# Mcu.net
KiCad netlist of a schematic drawn in Altium Designer
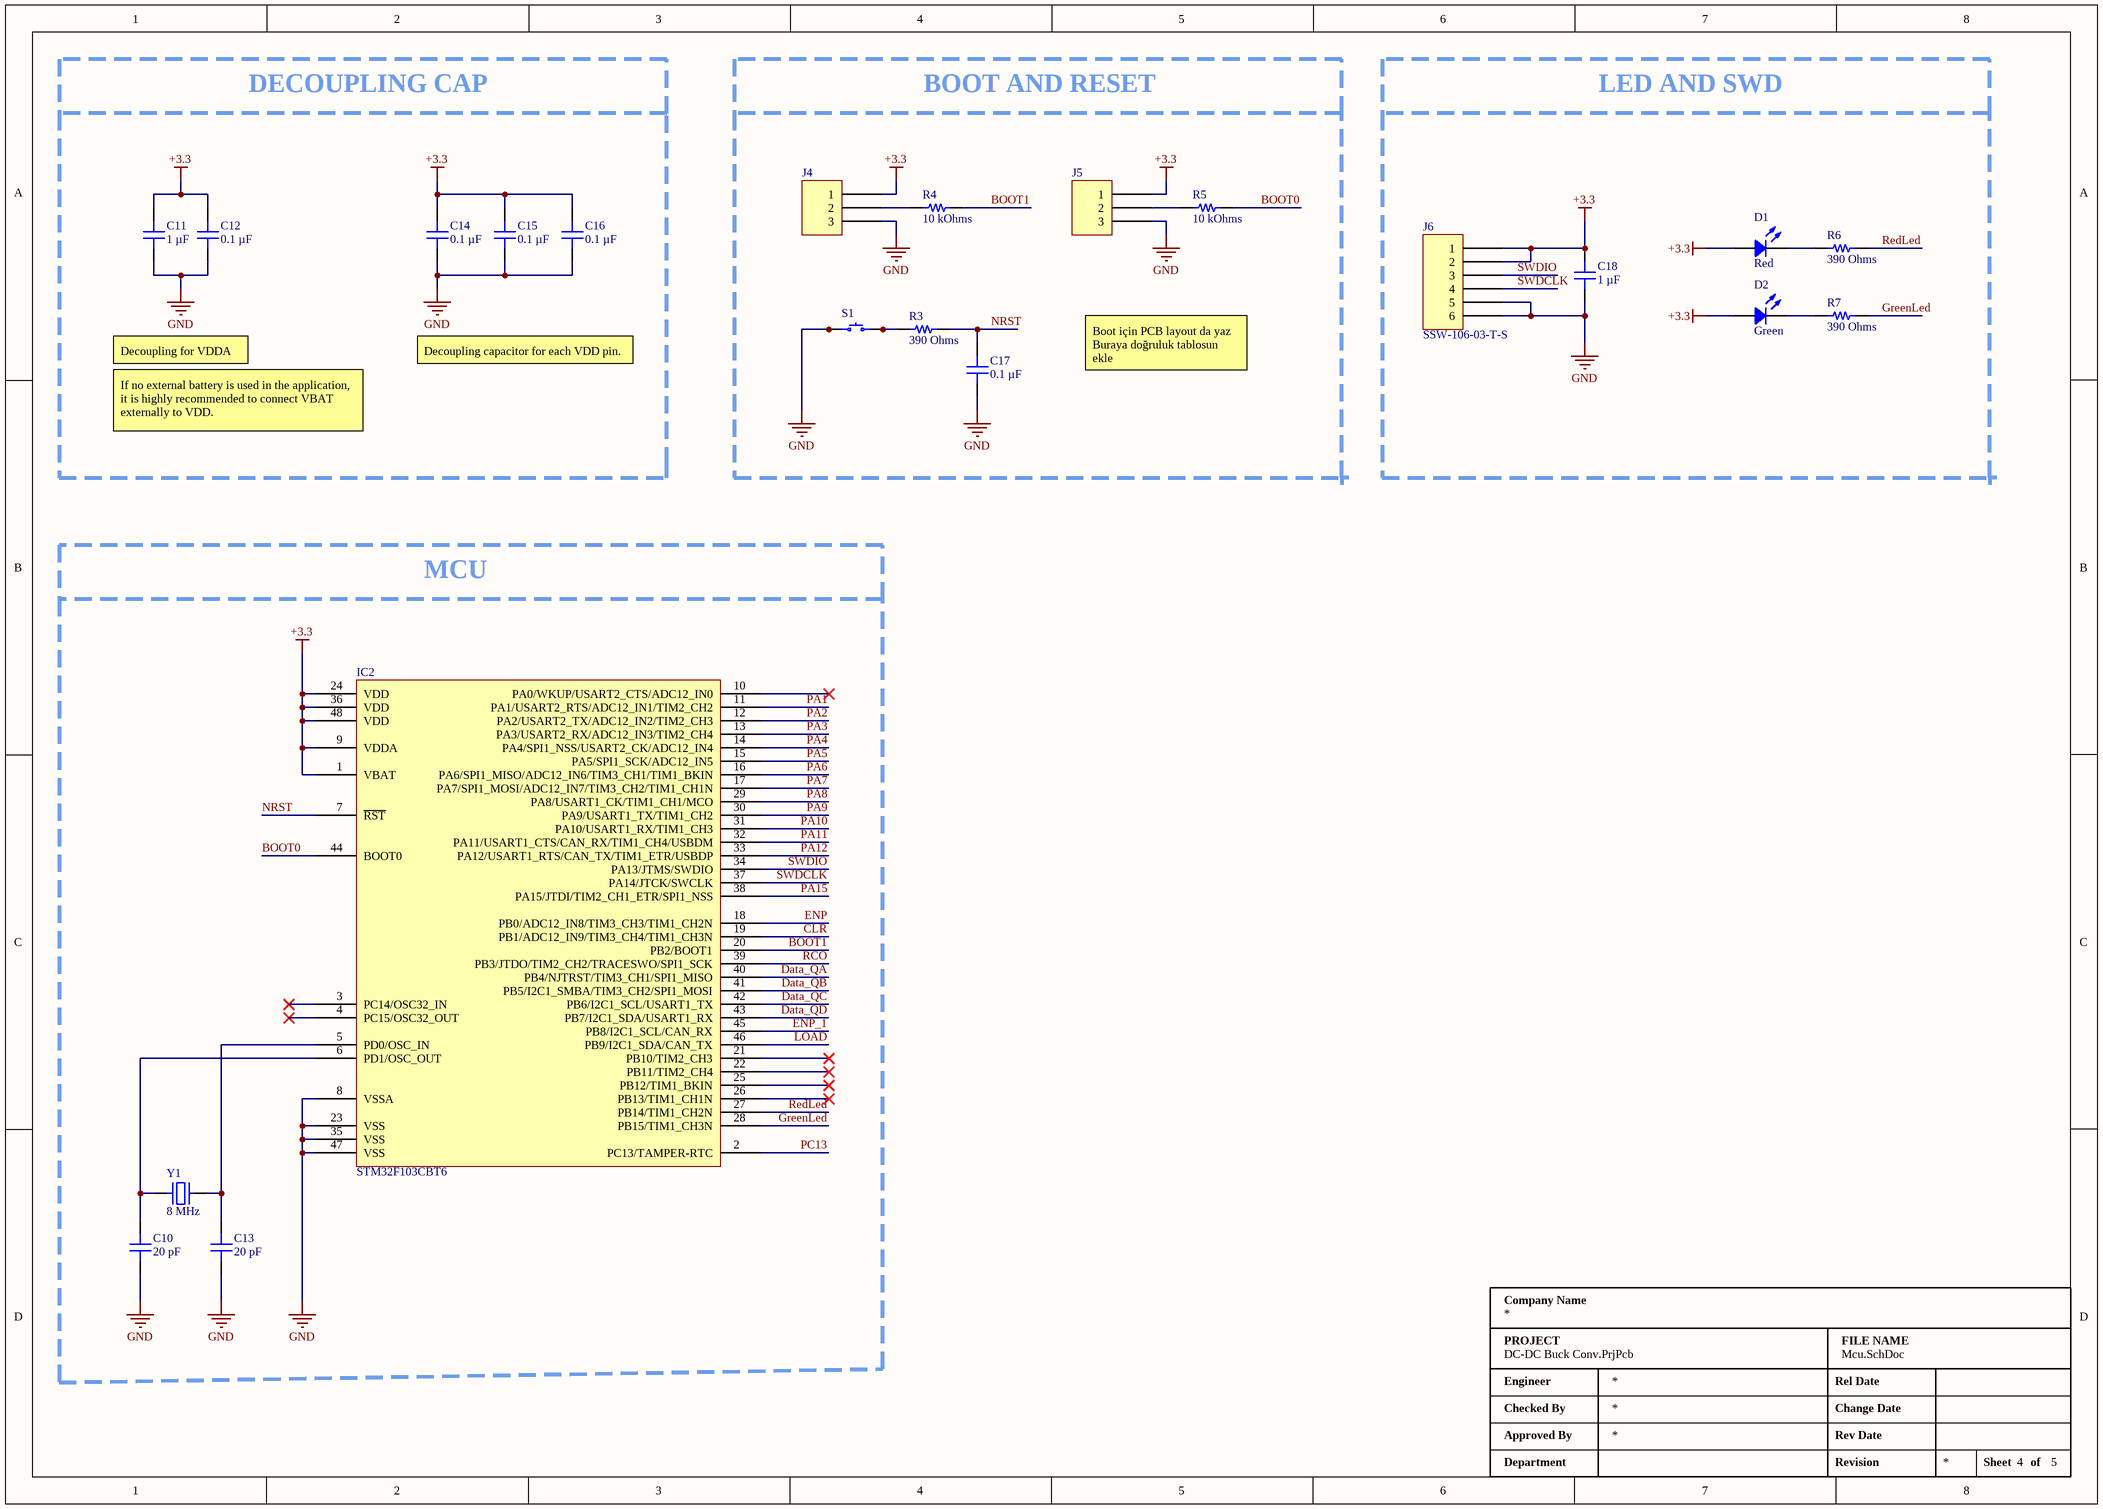
[diagram p0: Mcu.SchDoc]

(export (version "E")
  (design (tool "Eeschema 10.0.6"))
  (components
    (comp (ref "C10")
      (value "20 pF")
      (footprint "CAP 0805_2012")
      (description "CAP CER SMD 0805 20PF 50V 1% COG")
      (fields
        (field (name "PART NUMBER") "C0805C200F5GAC7800")
        (field (name "CAPACITANCE") "20 pF")
        (field (name "MANUFACTURER") "KEMET")
      )
      (libsource (lib "Celestial Altium Library - altium_library") (part "Capacitor"))
    )
    (comp (ref "C11")
      (value "1 µF")
      (footprint "CAP 0603_1608")
      (description "CAP CER 0603 1UF 16V X7R 20%")
      (fields
        (field (name "PART NUMBER") "C0603X105M4RAC7867")
        (field (name "CAPACITANCE") "1 µF")
        (field (name "MANUFACTURER") "KEMET")
      )
      (libsource (lib "Celestial Altium Library - altium_library") (part "Capacitor"))
    )
    (comp (ref "C12")
      (value "0.1 µF")
      (footprint "CAP 0805_2012")
      (description "CAP CER 0805 0.1UF 100V X7R 5%")
      (fields
        (field (name "PART NUMBER") "C0805C104J1RECAUTO")
        (field (name "CAPACITANCE") "0.1 µF")
        (field (name "MANUFACTURER") "KEMET")
      )
      (libsource (lib "Celestial Altium Library - altium_library") (part "Capacitor"))
    )
    (comp (ref "C13")
      (value "20 pF")
      (footprint "CAP 0805_2012")
      (description "CAP CER SMD 0805 20PF 50V 1% COG")
      (fields
        (field (name "PART NUMBER") "C0805C200F5GAC7800")
        (field (name "CAPACITANCE") "20 pF")
        (field (name "MANUFACTURER") "KEMET")
      )
      (libsource (lib "Celestial Altium Library - altium_library") (part "Capacitor"))
    )
    (comp (ref "C14")
      (value "0.1 µF")
      (footprint "CAP 0805_2012")
      (description "CAP CER 0805 0.1UF 100V X7R 5%")
      (fields
        (field (name "PART NUMBER") "C0805C104J1RECAUTO")
        (field (name "CAPACITANCE") "0.1 µF")
        (field (name "MANUFACTURER") "KEMET")
      )
      (libsource (lib "Celestial Altium Library - altium_library") (part "Capacitor"))
    )
    (comp (ref "C15")
      (value "0.1 µF")
      (footprint "CAP 0805_2012")
      (description "CAP CER 0805 0.1UF 100V X7R 5%")
      (fields
        (field (name "PART NUMBER") "C0805C104J1RECAUTO")
        (field (name "CAPACITANCE") "0.1 µF")
        (field (name "MANUFACTURER") "KEMET")
      )
      (libsource (lib "Celestial Altium Library - altium_library") (part "Capacitor"))
    )
    (comp (ref "C16")
      (value "0.1 µF")
      (footprint "CAP 0805_2012")
      (description "CAP CER 0805 0.1UF 100V X7R 5%")
      (fields
        (field (name "PART NUMBER") "C0805C104J1RECAUTO")
        (field (name "CAPACITANCE") "0.1 µF")
        (field (name "MANUFACTURER") "KEMET")
      )
      (libsource (lib "Celestial Altium Library - altium_library") (part "Capacitor"))
    )
    (comp (ref "C17")
      (value "0.1 µF")
      (footprint "CAP 0805_2012")
      (description "CAP CER 0805 0.1UF 100V X7R 5%")
      (fields
        (field (name "PART NUMBER") "C0805C104J1RECAUTO")
        (field (name "CAPACITANCE") "0.1 µF")
        (field (name "MANUFACTURER") "KEMET")
      )
      (libsource (lib "Celestial Altium Library - altium_library") (part "Capacitor"))
    )
    (comp (ref "C18")
      (value "1 µF")
      (footprint "CAP 0603_1608")
      (description "CAP CER 0603 1UF 16V X7R 20%")
      (fields
        (field (name "PART NUMBER") "C0603X105M4RAC7867")
        (field (name "CAPACITANCE") "1 µF")
        (field (name "MANUFACTURER") "KEMET")
      )
      (libsource (lib "Celestial Altium Library - altium_library") (part "Capacitor"))
    )
    (comp (ref "D1")
      (value "Red")
      (footprint "LED 0805_2012 RED")
      (description "LED RED CLEAR 0805 SMD")
      (fields
        (field (name "PART NUMBER") "CMD17-21SRC/TR8")
        (field (name "MANUFACTURER") "Visual Communications Company - VCC")
      )
      (libsource (lib "Celestial Altium Library - altium_library") (part "LED"))
    )
    (comp (ref "D2")
      (value "Green")
      (footprint "LED 0805_2012 RED")
      (description "LED RED CLEAR 0805 SMD")
      (fields
        (field (name "PART NUMBER") "CMD17-21SRC/TR8")
        (field (name "MANUFACTURER") "Visual Communications Company - VCC")
      )
      (libsource (lib "Celestial Altium Library - altium_library") (part "LED"))
    )
    (comp (ref "IC2")
      (value "STM32F103CBT6")
      (footprint "ST LQFP-48 7X7MM")
      (description "IC MCU 32BIT 128KB FLASH 48LQFP")
      (fields (field (name "MANUFACTURER") "STMicroelectronics"))
      (libsource (lib "Celestial Altium Library - altium_library") (part "ST STM32F103 48PIN"))
    )
    (comp (ref "J4")
      (value "61300311121")
      (footprint "WURTH WE-PHD 61300311121")
      (description "CONN HEADER VERT 3POS 2.54MM")
      (fields (field (name "MANUFACTURER") "Würth Elektronik"))
      (libsource (lib "Celestial Altium Library - altium_library") (part "3 Pin"))
    )
    (comp (ref "J5")
      (value "61300311121")
      (footprint "WURTH WE-PHD 61300311121")
      (description "CONN HEADER VERT 3POS 2.54MM")
      (fields (field (name "MANUFACTURER") "Würth Elektronik"))
      (libsource (lib "Celestial Altium Library - altium_library") (part "3 Pin"))
    )
    (comp (ref "J6")
      (value "SSW-106-03-T-S")
      (footprint "SAMTEC SSW-106-03-T-S")
      (description "CONN RCPT 6POS 0.1 TIN PCB")
      (fields (field (name "MANUFACTURER") "Samtec Inc."))
      (libsource (lib "Celestial Altium Library - altium_library") (part "6 Pin"))
    )
    (comp (ref "R3")
      (value "390 Ohms")
      (footprint "KOA RES RK73 RN73 0603_1608")
      (description "RESISTOR")
      (fields
        (field (name "PART NUMBER") "RK73B1JTTDD391J")
        (field (name "MANUFACTURER") "KOA Speer Electronics, Inc.")
      )
      (libsource (lib "Celestial Altium Library - altium_library") (part "Resistor"))
    )
    (comp (ref "R4")
      (value "10 kOhms")
      (footprint "YAGEO RES 0603_1608")
      (description "RES SMD 10K OHM 1% 1/10W 0603")
      (fields (field (name "PART NUMBER") "AT0603FRE0710KL") (field (name "MANUFACTURER") "Yageo"))
      (libsource (lib "Celestial Altium Library - altium_library") (part "Resistor"))
    )
    (comp (ref "R5")
      (value "10 kOhms")
      (footprint "YAGEO RES 0603_1608")
      (description "RES SMD 10K OHM 1% 1/10W 0603")
      (fields (field (name "PART NUMBER") "AT0603FRE0710KL") (field (name "MANUFACTURER") "Yageo"))
      (libsource (lib "Celestial Altium Library - altium_library") (part "Resistor"))
    )
    (comp (ref "R6")
      (value "390 Ohms")
      (footprint "KOA RES RK73 RN73 0603_1608")
      (description "RESISTOR")
      (fields
        (field (name "PART NUMBER") "RK73B1JTTDD391J")
        (field (name "MANUFACTURER") "KOA Speer Electronics, Inc.")
      )
      (libsource (lib "Celestial Altium Library - altium_library") (part "Resistor"))
    )
    (comp (ref "R7")
      (value "390 Ohms")
      (footprint "KOA RES RK73 RN73 0603_1608")
      (description "RESISTOR")
      (fields
        (field (name "PART NUMBER") "RK73B1JTTDD391J")
        (field (name "MANUFACTURER") "KOA Speer Electronics, Inc.")
      )
      (libsource (lib "Celestial Altium Library - altium_library") (part "Resistor"))
    )
    (comp (ref "S1")
      (value "PTS645SM43SMTR92 LFS")
      (footprint "C&K PTS645")
      (description "SWITCH TACTILE SPST-NO 0.05A 12V")
      (fields (field (name "MANUFACTURER") "C&K"))
      (libsource (lib "Celestial Altium Library - altium_library") (part "SPST-NO 4 PIN"))
    )
    (comp (ref "Y1")
      (value "8 MHz")
      (footprint "NDK NX5032GA")
      (description "CRYSTAL 8.0000MHZ 18PF SMD")
      (fields
        (field (name "PART NUMBER") "NX5032GA-8MHZ-EXS00A-CG07039")
        (field (name "MANUFACTURER") "NDK America, Inc.")
      )
      (libsource (lib "Celestial Altium Library - altium_library") (part "NDK Crystal NX5032GA"))
    )
  )
  (nets
    (net (code "1") (name "+3.3") (class "Default")
      (node (ref "C11") (pin "2") (pinfunction "2_2") (pintype "passive"))
      (node (ref "C12") (pin "2") (pinfunction "2_2") (pintype "passive"))
      (node (ref "C14") (pin "2") (pinfunction "2_2") (pintype "passive"))
      (node (ref "C15") (pin "2") (pinfunction "2_2") (pintype "passive"))
      (node (ref "C16") (pin "2") (pinfunction "2_2") (pintype "passive"))
      (node (ref "C18") (pin "2") (pinfunction "2_2") (pintype "passive"))
      (node (ref "D1") (pin "1") (pinfunction "1_1") (pintype "passive"))
      (node (ref "D2") (pin "1") (pinfunction "1_1") (pintype "passive"))
      (node (ref "IC2") (pin "1") (pinfunction "VBAT_1") (pintype "passive"))
      (node (ref "IC2") (pin "24") (pinfunction "VDD_24") (pintype "passive"))
      (node (ref "IC2") (pin "36") (pinfunction "VDD_36") (pintype "passive"))
      (node (ref "IC2") (pin "48") (pinfunction "VDD_48") (pintype "passive"))
      (node (ref "IC2") (pin "9") (pinfunction "VDDA_9") (pintype "passive"))
      (node (ref "J4") (pin "1") (pinfunction "1_1") (pintype "passive"))
      (node (ref "J5") (pin "1") (pinfunction "1_1") (pintype "passive"))
      (node (ref "J6") (pin "1") (pinfunction "1_1") (pintype "passive"))
      (node (ref "J6") (pin "2") (pinfunction "2_2") (pintype "passive"))
    )
    (net (code "2") (name "/BOOT0") (class "Default")
      (node (ref "IC2") (pin "44") (pinfunction "BOOT0_44") (pintype "passive"))
      (node (ref "R5") (pin "2") (pinfunction "2_2") (pintype "passive"))
    )
    (net (code "3") (name "/BOOT1") (class "Default")
      (node (ref "IC2") (pin "20") (pinfunction "PB2/BOOT1_20") (pintype "passive"))
      (node (ref "R4") (pin "2") (pinfunction "2_2") (pintype "passive"))
    )
    (net (code "4") (name "/CLR") (class "Default")
      (node (ref "IC2") (pin "19") (pinfunction "PB1/ADC12_IN9/TIM3_CH4/TIM1_CH3N_19") (pintype "passive"))
    )
    (net (code "5") (name "/Data_QA") (class "Default")
      (node (ref "IC2") (pin "40") (pinfunction "PB4/NJTRST/TIM3_CH1/SPI1_MISO_40") (pintype "passive"))
    )
    (net (code "6") (name "/Data_QB") (class "Default")
      (node (ref "IC2") (pin "41") (pinfunction "PB5/I2C1_SMBA/TIM3_CH2/SPI1_MOSI_41") (pintype "passive"))
    )
    (net (code "7") (name "/Data_QC") (class "Default")
      (node (ref "IC2") (pin "42") (pinfunction "PB6/I2C1_SCL/USART1_TX_42") (pintype "passive"))
    )
    (net (code "8") (name "/Data_QD") (class "Default")
      (node (ref "IC2") (pin "43") (pinfunction "PB7/I2C1_SDA/USART1_RX_43") (pintype "passive"))
    )
    (net (code "9") (name "/ENP") (class "Default")
      (node (ref "IC2") (pin "18") (pinfunction "PB0/ADC12_IN8/TIM3_CH3/TIM1_CH2N_18") (pintype "passive"))
    )
    (net (code "10") (name "/ENP_1") (class "Default")
      (node (ref "IC2") (pin "45") (pinfunction "PB8/I2C1_SCL/CAN_RX_45") (pintype "passive"))
    )
    (net (code "11") (name "/GreenLed") (class "Default")
      (node (ref "IC2") (pin "28") (pinfunction "PB15/TIM1_CH3N_28") (pintype "passive"))
      (node (ref "R7") (pin "1") (pinfunction "1_1") (pintype "passive"))
    )
    (net (code "12") (name "/LOAD") (class "Default")
      (node (ref "IC2") (pin "46") (pinfunction "PB9/I2C1_SDA/CAN_TX_46") (pintype "passive"))
    )
    (net (code "13") (name "/NRST") (class "Default")
      (node (ref "C17") (pin "1") (pinfunction "1_1") (pintype "passive"))
      (node (ref "IC2") (pin "7") (pinfunction "~{RST}_7") (pintype "passive"))
      (node (ref "R3") (pin "2") (pinfunction "2_2") (pintype "passive"))
    )
    (net (code "14") (name "/PA1") (class "Default")
      (node (ref "IC2") (pin "11") (pinfunction "PA1/USART2_RTS/ADC12_IN1/TIM2_CH2_11") (pintype "passive"))
    )
    (net (code "15") (name "/PA2") (class "Default")
      (node (ref "IC2") (pin "12") (pinfunction "PA2/USART2_TX/ADC12_IN2/TIM2_CH3_12") (pintype "passive"))
    )
    (net (code "16") (name "/PA3") (class "Default")
      (node (ref "IC2") (pin "13") (pinfunction "PA3/USART2_RX/ADC12_IN3/TIM2_CH4_13") (pintype "passive"))
    )
    (net (code "17") (name "/PA4") (class "Default")
      (node (ref "IC2") (pin "14") (pinfunction "PA4/SPI1_NSS/USART2_CK/ADC12_IN4_14") (pintype "passive"))
    )
    (net (code "18") (name "/PA5") (class "Default")
      (node (ref "IC2") (pin "15") (pinfunction "PA5/SPI1_SCK/ADC12_IN5_15") (pintype "passive"))
    )
    (net (code "19") (name "/PA6") (class "Default")
      (node (ref "IC2") (pin "16") (pinfunction "PA6/SPI1_MISO/ADC12_IN6/TIM3_CH1/TIM1_BKIN_16") (pintype "passive"))
    )
    (net (code "20") (name "/PA7") (class "Default")
      (node (ref "IC2") (pin "17") (pinfunction "PA7/SPI1_MOSI/ADC12_IN7/TIM3_CH2/TIM1_CH1N_17") (pintype "passive"))
    )
    (net (code "21") (name "/PA8") (class "Default")
      (node (ref "IC2") (pin "29") (pinfunction "PA8/USART1_CK/TIM1_CH1/MCO_29") (pintype "passive"))
    )
    (net (code "22") (name "/PA9") (class "Default")
      (node (ref "IC2") (pin "30") (pinfunction "PA9/USART1_TX/TIM1_CH2_30") (pintype "passive"))
    )
    (net (code "23") (name "/PA10") (class "Default")
      (node (ref "IC2") (pin "31") (pinfunction "PA10/USART1_RX/TIM1_CH3_31") (pintype "passive"))
    )
    (net (code "24") (name "/PA11") (class "Default")
      (node (ref "IC2") (pin "32") (pinfunction "PA11/USART1_CTS/CAN_RX/TIM1_CH4/USBDM_32") (pintype "passive"))
    )
    (net (code "25") (name "/PA12") (class "Default")
      (node (ref "IC2") (pin "33") (pinfunction "PA12/USART1_RTS/CAN_TX/TIM1_ETR/USBDP_33") (pintype "passive"))
    )
    (net (code "26") (name "/PA15") (class "Default")
      (node (ref "IC2") (pin "38") (pinfunction "PA15/JTDI/TIM2_CH1_ETR/SPI1_NSS_38") (pintype "passive"))
    )
    (net (code "27") (name "/PC13") (class "Default")
      (node (ref "IC2") (pin "2") (pinfunction "PC13/TAMPER-RTC_2") (pintype "passive"))
    )
    (net (code "28") (name "/RCO") (class "Default")
      (node (ref "IC2") (pin "39") (pinfunction "PB3/JTDO/TIM2_CH2/TRACESWO/SPI1_SCK_39") (pintype "passive"))
    )
    (net (code "29") (name "/RedLed") (class "Default")
      (node (ref "IC2") (pin "27") (pinfunction "PB14/TIM1_CH2N_27") (pintype "passive"))
      (node (ref "R6") (pin "1") (pinfunction "1_1") (pintype "passive"))
    )
    (net (code "30") (name "/SWDCLK") (class "Default")
      (node (ref "IC2") (pin "37") (pinfunction "PA14/JTCK/SWCLK_37") (pintype "passive"))
      (node (ref "J6") (pin "4") (pinfunction "4_4") (pintype "passive"))
    )
    (net (code "31") (name "/SWDIO") (class "Default")
      (node (ref "IC2") (pin "34") (pinfunction "PA13/JTMS/SWDIO_34") (pintype "passive"))
      (node (ref "J6") (pin "3") (pinfunction "3_3") (pintype "passive"))
    )
    (net (code "32") (name "GND") (class "Default")
      (node (ref "C10") (pin "1") (pinfunction "1_1") (pintype "passive"))
      (node (ref "C11") (pin "1") (pinfunction "1_1") (pintype "passive"))
      (node (ref "C12") (pin "1") (pinfunction "1_1") (pintype "passive"))
      (node (ref "C13") (pin "1") (pinfunction "1_1") (pintype "passive"))
      (node (ref "C14") (pin "1") (pinfunction "1_1") (pintype "passive"))
      (node (ref "C15") (pin "1") (pinfunction "1_1") (pintype "passive"))
      (node (ref "C16") (pin "1") (pinfunction "1_1") (pintype "passive"))
      (node (ref "C17") (pin "2") (pinfunction "2_2") (pintype "passive"))
      (node (ref "C18") (pin "1") (pinfunction "1_1") (pintype "passive"))
      (node (ref "IC2") (pin "23") (pinfunction "VSS_23") (pintype "passive"))
      (node (ref "IC2") (pin "35") (pinfunction "VSS_35") (pintype "passive"))
      (node (ref "IC2") (pin "47") (pinfunction "VSS_47") (pintype "passive"))
      (node (ref "IC2") (pin "8") (pinfunction "VSSA_8") (pintype "passive"))
      (node (ref "J4") (pin "3") (pinfunction "3_3") (pintype "passive"))
      (node (ref "J5") (pin "3") (pinfunction "3_3") (pintype "passive"))
      (node (ref "J6") (pin "5") (pinfunction "5_5") (pintype "passive"))
      (node (ref "J6") (pin "6") (pinfunction "6_6") (pintype "passive"))
      (node (ref "S1") (pin "1") (pinfunction "1_1") (pintype "passive"))
      (node (ref "S1") (pin "2") (pinfunction "2_2") (pintype "passive"))
    )
    (net (code "33") (name "Net-(D1-Pad2)") (class "Default")
      (node (ref "D1") (pin "2") (pinfunction "2_2") (pintype "passive"))
      (node (ref "R6") (pin "2") (pinfunction "2_2") (pintype "passive"))
    )
    (net (code "34") (name "Net-(D2-Pad2)") (class "Default")
      (node (ref "D2") (pin "2") (pinfunction "2_2") (pintype "passive"))
      (node (ref "R7") (pin "2") (pinfunction "2_2") (pintype "passive"))
    )
    (net (code "35") (name "Net-(IC2-PD0{slash}OSC_IN)") (class "Default")
      (node (ref "C13") (pin "2") (pinfunction "2_2") (pintype "passive"))
      (node (ref "IC2") (pin "5") (pinfunction "PD0/OSC_IN_5") (pintype "passive"))
      (node (ref "Y1") (pin "1") (pinfunction "1_1") (pintype "passive"))
    )
    (net (code "36") (name "Net-(IC2-PD1{slash}OSC_OUT)") (class "Default")
      (node (ref "C10") (pin "2") (pinfunction "2_2") (pintype "passive"))
      (node (ref "IC2") (pin "6") (pinfunction "PD1/OSC_OUT_6") (pintype "passive"))
      (node (ref "Y1") (pin "2") (pinfunction "2_2") (pintype "passive"))
    )
    (net (code "37") (name "Net-(J4-Pad2)") (class "Default")
      (node (ref "J4") (pin "2") (pinfunction "2_2") (pintype "passive"))
      (node (ref "R4") (pin "1") (pinfunction "1_1") (pintype "passive"))
    )
    (net (code "38") (name "Net-(J5-Pad2)") (class "Default")
      (node (ref "J5") (pin "2") (pinfunction "2_2") (pintype "passive"))
      (node (ref "R5") (pin "1") (pinfunction "1_1") (pintype "passive"))
    )
    (net (code "39") (name "Net-(R3-Pad1)") (class "Default")
      (node (ref "R3") (pin "1") (pinfunction "1_1") (pintype "passive"))
      (node (ref "S1") (pin "3") (pinfunction "3_3") (pintype "passive"))
      (node (ref "S1") (pin "4") (pinfunction "4_4") (pintype "passive"))
    )
    (net (code "40") (name "unconnected-(IC2-PA0{slash}WKUP{slash}USART2_CTS{slash}ADC12_IN0-Pad10)") (class "Default")
      (node (ref "IC2") (pin "10") (pinfunction "PA0/WKUP/USART2_CTS/ADC12_IN0_10") (pintype "passive+no_connect"))
    )
    (net (code "41") (name "unconnected-(IC2-PB10{slash}TIM2_CH3-Pad21)") (class "Default")
      (node (ref "IC2") (pin "21") (pinfunction "PB10/TIM2_CH3_21") (pintype "passive+no_connect"))
    )
    (net (code "42") (name "unconnected-(IC2-PB11{slash}TIM2_CH4-Pad22)") (class "Default")
      (node (ref "IC2") (pin "22") (pinfunction "PB11/TIM2_CH4_22") (pintype "passive+no_connect"))
    )
    (net (code "43") (name "unconnected-(IC2-PB12{slash}TIM1_BKIN-Pad25)") (class "Default")
      (node (ref "IC2") (pin "25") (pinfunction "PB12/TIM1_BKIN_25") (pintype "passive+no_connect"))
    )
    (net (code "44") (name "unconnected-(IC2-PB13{slash}TIM1_CH1N-Pad26)") (class "Default")
      (node (ref "IC2") (pin "26") (pinfunction "PB13/TIM1_CH1N_26") (pintype "passive+no_connect"))
    )
    (net (code "45") (name "unconnected-(IC2-PC14{slash}OSC32_IN-Pad3)") (class "Default")
      (node (ref "IC2") (pin "3") (pinfunction "PC14/OSC32_IN_3") (pintype "passive+no_connect"))
    )
    (net (code "46") (name "unconnected-(IC2-PC15{slash}OSC32_OUT-Pad4)") (class "Default")
      (node (ref "IC2") (pin "4") (pinfunction "PC15/OSC32_OUT_4") (pintype "passive+no_connect"))
    )
  )
)
